# Controller_Keinz_2022.net
KiCad netlist of a schematic drawn in EAGLE
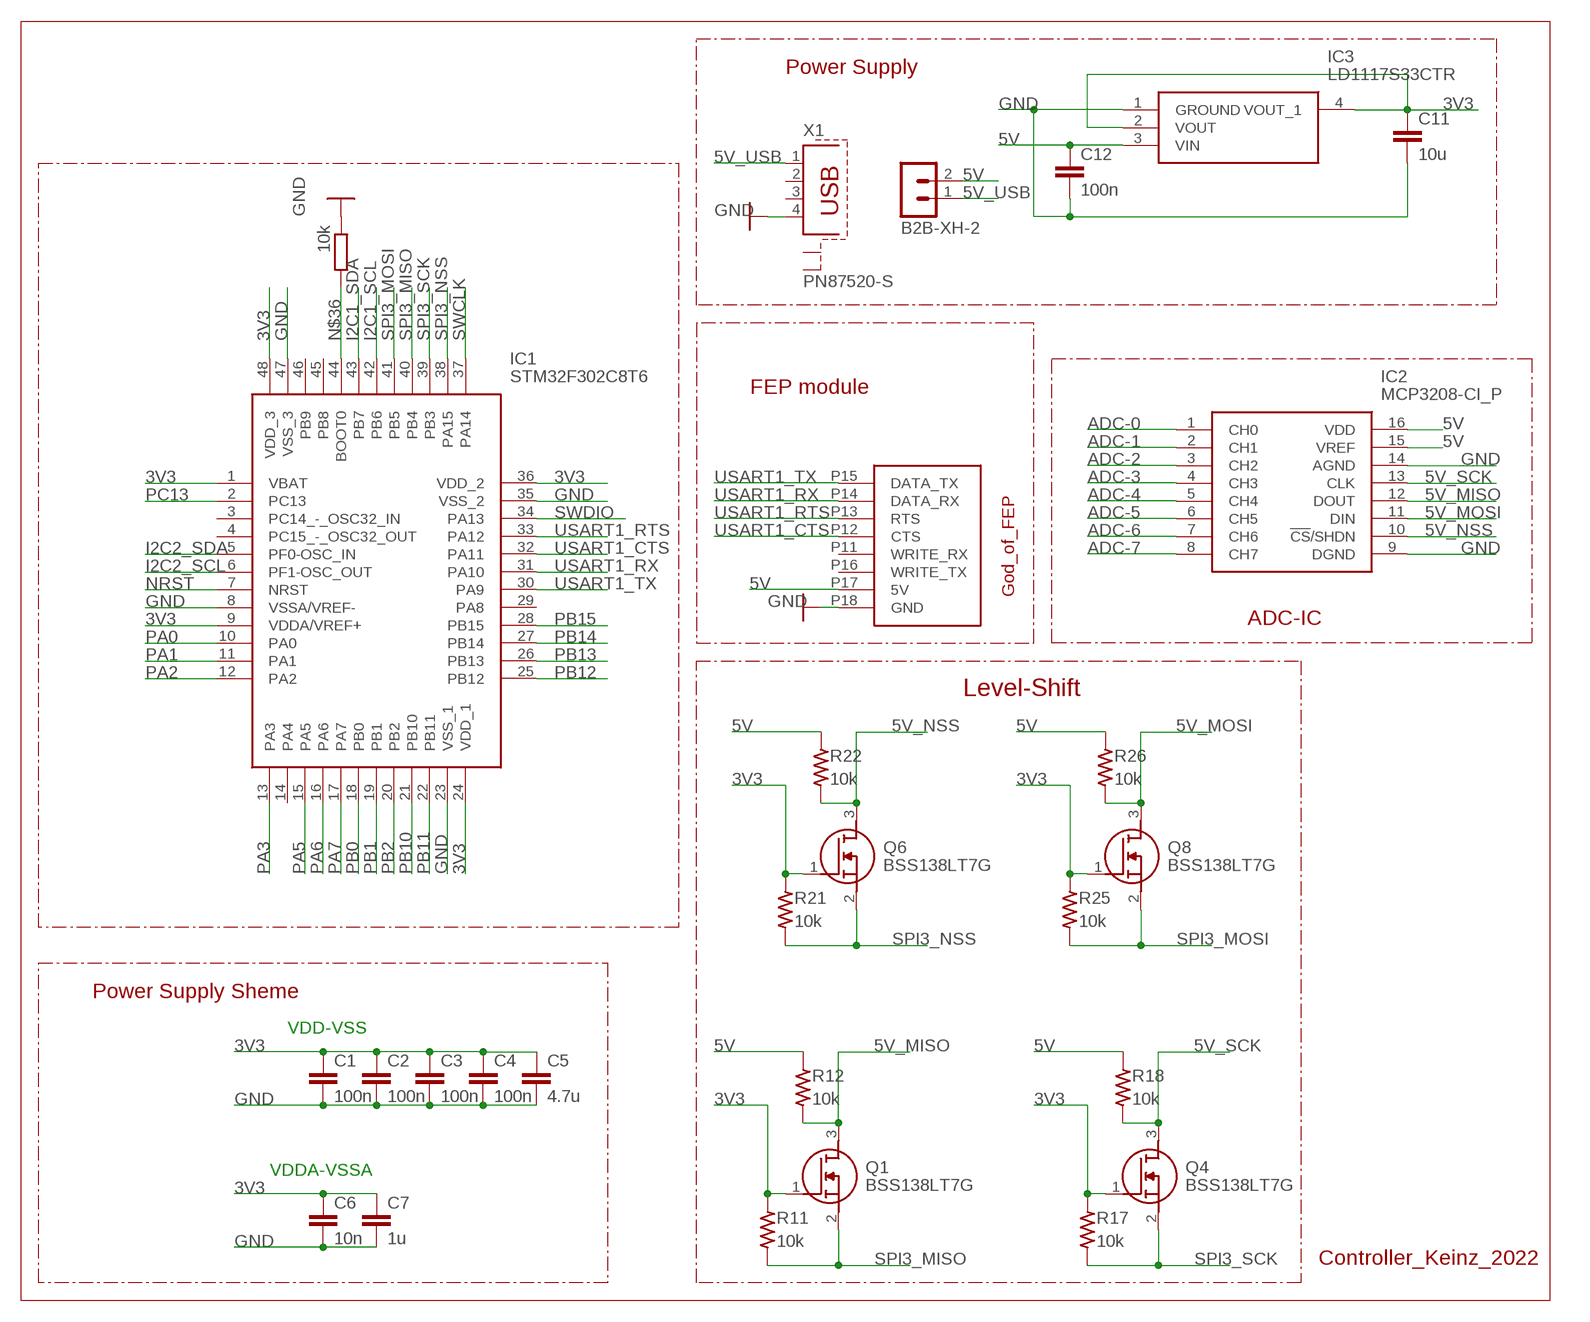
[diagram p0: schematic, sheet 1]
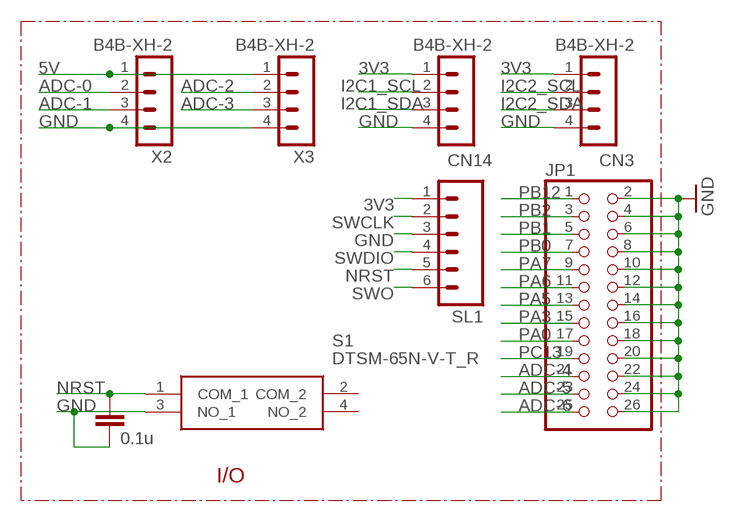
[diagram p1: schematic, sheet 2]
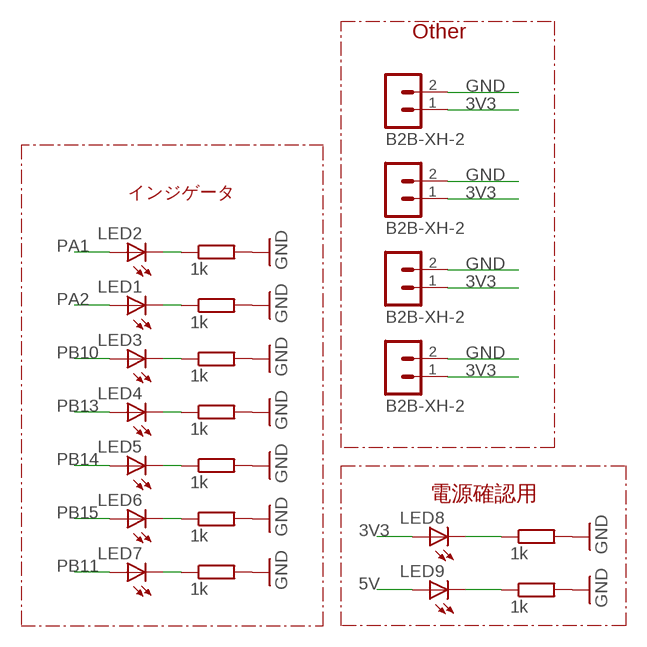
[diagram p2: schematic, sheet 3]

(export (version "E")
  (design (tool "Eeschema 10.0.6"))
  (components
    (comp (ref "C1")
      (value "100n")
      (footprint "eagle-import:C0603K")
      (libsource (lib "eagle-import") (part "C-EUC0603K"))
    )
    (comp (ref "C2")
      (value "100n")
      (footprint "eagle-import:C0603K")
      (libsource (lib "eagle-import") (part "C-EUC0603K"))
    )
    (comp (ref "C3")
      (value "100n")
      (footprint "eagle-import:C0603K")
      (libsource (lib "eagle-import") (part "C-EUC0603K"))
    )
    (comp (ref "C4")
      (value "100n")
      (footprint "eagle-import:C0603K")
      (libsource (lib "eagle-import") (part "C-EUC0603K"))
    )
    (comp (ref "C5")
      (value "4.7u")
      (footprint "eagle-import:C0603K")
      (libsource (lib "eagle-import") (part "C-EUC0603K"))
    )
    (comp (ref "C6")
      (value "10n")
      (footprint "eagle-import:C0603K")
      (libsource (lib "eagle-import") (part "C-EUC0603K"))
    )
    (comp (ref "C7")
      (value "1u")
      (footprint "eagle-import:C0603K")
      (libsource (lib "eagle-import") (part "C-EUC0603K"))
    )
    (comp (ref "C11")
      (value "10u")
      (footprint "eagle-import:C0603K")
      (libsource (lib "eagle-import") (part "C-EUC0603K"))
    )
    (comp (ref "C12")
      (value "100n")
      (footprint "eagle-import:C0603K")
      (libsource (lib "eagle-import") (part "C-EUC0603K"))
    )
    (comp (ref "FEP_1")
      (value "GOD_OF_FEP")
      (footprint "eagle-import:GOD_OF_FEP")
      (libsource (lib "eagle-import") (part "GOD_OF_FEP"))
    )
    (comp (ref "IC1")
      (value "STM32F302C8T6")
      (footprint "eagle-import:QFP50P900X900X160-48N")
      (fields (field (name "MOUSER_PART_NUMBER") "511-STM32F302C8T6"))
      (libsource (lib "eagle-import") (part "STM32F302C8T6"))
    )
    (comp (ref "IC2")
      (value "MCP3208-CI_P")
      (footprint "eagle-import:DIP781W56P254L1918H533Q16N")
      (fields
        (field (name "ARROW_PART_NUMBER") "MCP3208-CI/P")
        (field (name "MOUSER_PART_NUMBER") "579-MCP3208CIP")
      )
      (libsource (lib "eagle-import") (part "MCP3208-CI_P"))
    )
    (comp (ref "IC3")
      (value "LD1117S33CTR")
      (footprint "eagle-import:SOT230P700X190-4N")
      (fields (field (name "MOUSER_PART_NUMBER") "511-LD1117S33C") (field (name "RS_PART_NUMBER") "6869388P"))
      (libsource (lib "eagle-import") (part "LD1117S33CTR"))
    )
    (comp (ref "Q1")
      (value "BSS138LT7G")
      (footprint "eagle-import:SOT96P237X111-3N")
      (fields (field (name "MOUSER_PART_NUMBER") "863-BSS138LT7G"))
      (libsource (lib "eagle-import") (part "BSS138LT7G"))
    )
    (comp (ref "Q4")
      (value "BSS138LT7G")
      (footprint "eagle-import:SOT96P237X111-3N")
      (fields (field (name "MOUSER_PART_NUMBER") "863-BSS138LT7G"))
      (libsource (lib "eagle-import") (part "BSS138LT7G"))
    )
    (comp (ref "Q6")
      (value "BSS138LT7G")
      (footprint "eagle-import:SOT96P237X111-3N")
      (fields (field (name "MOUSER_PART_NUMBER") "863-BSS138LT7G"))
      (libsource (lib "eagle-import") (part "BSS138LT7G"))
    )
    (comp (ref "Q8")
      (value "BSS138LT7G")
      (footprint "eagle-import:SOT96P237X111-3N")
      (fields (field (name "MOUSER_PART_NUMBER") "863-BSS138LT7G"))
      (libsource (lib "eagle-import") (part "BSS138LT7G"))
    )
    (comp (ref "R8")
      (value "10k")
      (footprint "eagle-import:R0603@1")
      (libsource (lib "eagle-import") (part "R-EU_R0603"))
    )
    (comp (ref "R11")
      (value "10k")
      (footprint "eagle-import:SMD1608")
      (libsource (lib "eagle-import") (part "RESISTOR-US1608"))
    )
    (comp (ref "R12")
      (value "10k")
      (footprint "eagle-import:SMD1608")
      (libsource (lib "eagle-import") (part "RESISTOR-US1608"))
    )
    (comp (ref "R17")
      (value "10k")
      (footprint "eagle-import:SMD1608")
      (libsource (lib "eagle-import") (part "RESISTOR-US1608"))
    )
    (comp (ref "R18")
      (value "10k")
      (footprint "eagle-import:SMD1608")
      (libsource (lib "eagle-import") (part "RESISTOR-US1608"))
    )
    (comp (ref "R21")
      (value "10k")
      (footprint "eagle-import:SMD1608")
      (libsource (lib "eagle-import") (part "RESISTOR-US1608"))
    )
    (comp (ref "R22")
      (value "10k")
      (footprint "eagle-import:SMD1608")
      (libsource (lib "eagle-import") (part "RESISTOR-US1608"))
    )
    (comp (ref "R25")
      (value "10k")
      (footprint "eagle-import:SMD1608")
      (libsource (lib "eagle-import") (part "RESISTOR-US1608"))
    )
    (comp (ref "R26")
      (value "10k")
      (footprint "eagle-import:SMD1608")
      (libsource (lib "eagle-import") (part "RESISTOR-US1608"))
    )
    (comp (ref "X1")
      (value "PN87520-S")
      (footprint "eagle-import:PN87520-S")
      (libsource (lib "eagle-import") (part "PN87520-S"))
    )
    (comp (ref "X22")
      (value "B2B-XH-2")
      (footprint "eagle-import:B2B-XH-A")
      (libsource (lib "eagle-import") (part "B2B-XH-2"))
    )
    (comp (ref "LED1")
      (value "LEDCHIP-LED0805")
      (footprint "eagle-import:CHIP-LED0805")
      (libsource (lib "eagle-import") (part "LEDCHIP-LED0805"))
    )
    (comp (ref "LED2")
      (value "LEDCHIP-LED0805")
      (footprint "eagle-import:CHIP-LED0805")
      (libsource (lib "eagle-import") (part "LEDCHIP-LED0805"))
    )
    (comp (ref "LED3")
      (value "LEDCHIP-LED0805")
      (footprint "eagle-import:CHIP-LED0805")
      (libsource (lib "eagle-import") (part "LEDCHIP-LED0805"))
    )
    (comp (ref "LED4")
      (value "LEDCHIP-LED0805")
      (footprint "eagle-import:CHIP-LED0805")
      (libsource (lib "eagle-import") (part "LEDCHIP-LED0805"))
    )
    (comp (ref "LED5")
      (value "LEDCHIP-LED0805")
      (footprint "eagle-import:CHIP-LED0805")
      (libsource (lib "eagle-import") (part "LEDCHIP-LED0805"))
    )
    (comp (ref "LED6")
      (value "LEDCHIP-LED0805")
      (footprint "eagle-import:CHIP-LED0805")
      (libsource (lib "eagle-import") (part "LEDCHIP-LED0805"))
    )
    (comp (ref "LED7")
      (value "LEDCHIP-LED0805")
      (footprint "eagle-import:CHIP-LED0805")
      (libsource (lib "eagle-import") (part "LEDCHIP-LED0805"))
    )
    (comp (ref "LED8")
      (value "LEDCHIP-LED0805")
      (footprint "eagle-import:CHIP-LED0805")
      (libsource (lib "eagle-import") (part "LEDCHIP-LED0805"))
    )
    (comp (ref "LED9")
      (value "LEDCHIP-LED0805")
      (footprint "eagle-import:CHIP-LED0805")
      (libsource (lib "eagle-import") (part "LEDCHIP-LED0805"))
    )
    (comp (ref "R1")
      (value "1k")
      (footprint "eagle-import:R0603@1")
      (libsource (lib "eagle-import") (part "R-EU_R0603"))
    )
    (comp (ref "R2")
      (value "1k")
      (footprint "eagle-import:R0603@1")
      (libsource (lib "eagle-import") (part "R-EU_R0603"))
    )
    (comp (ref "R3")
      (value "1k")
      (footprint "eagle-import:R0603@1")
      (libsource (lib "eagle-import") (part "R-EU_R0603"))
    )
    (comp (ref "R4")
      (value "1k")
      (footprint "eagle-import:R0603@1")
      (libsource (lib "eagle-import") (part "R-EU_R0603"))
    )
    (comp (ref "R5")
      (value "1k")
      (footprint "eagle-import:R0603@1")
      (libsource (lib "eagle-import") (part "R-EU_R0603"))
    )
    (comp (ref "R6")
      (value "1k")
      (footprint "eagle-import:R0603@1")
      (libsource (lib "eagle-import") (part "R-EU_R0603"))
    )
    (comp (ref "R7")
      (value "1k")
      (footprint "eagle-import:R0603@1")
      (libsource (lib "eagle-import") (part "R-EU_R0603"))
    )
    (comp (ref "R9")
      (value "1k")
      (footprint "eagle-import:R0603@1")
      (libsource (lib "eagle-import") (part "R-EU_R0603"))
    )
    (comp (ref "R10")
      (value "1k")
      (footprint "eagle-import:R0603@1")
      (libsource (lib "eagle-import") (part "R-EU_R0603"))
    )
    (comp (ref "X4")
      (value "B2B-XH-2")
      (footprint "eagle-import:B2B-XH-A")
      (libsource (lib "eagle-import") (part "B2B-XH-2"))
    )
    (comp (ref "X5")
      (value "B2B-XH-2")
      (footprint "eagle-import:B2B-XH-A")
      (libsource (lib "eagle-import") (part "B2B-XH-2"))
    )
    (comp (ref "X6")
      (value "B2B-XH-2")
      (footprint "eagle-import:B2B-XH-A")
      (libsource (lib "eagle-import") (part "B2B-XH-2"))
    )
    (comp (ref "X7")
      (value "B2B-XH-2")
      (footprint "eagle-import:B2B-XH-A")
      (libsource (lib "eagle-import") (part "B2B-XH-2"))
    )
    (comp (ref "C13")
      (value "0.1u")
      (footprint "eagle-import:C0603K")
      (libsource (lib "eagle-import") (part "C-EUC0603K"))
    )
    (comp (ref "CN3")
      (value "B4B-XH-2")
      (footprint "eagle-import:B4B-XH-A")
      (libsource (lib "eagle-import") (part "B4B-XH-2"))
    )
    (comp (ref "CN14")
      (value "B4B-XH-2")
      (footprint "eagle-import:B4B-XH-A")
      (libsource (lib "eagle-import") (part "B4B-XH-2"))
    )
    (comp (ref "JP1")
      (value "PINHD-2X13")
      (footprint "eagle-import:2X13")
      (libsource (lib "eagle-import") (part "PINHD-2X13"))
    )
    (comp (ref "S1")
      (value "DTSM-65N-V-T_R")
      (footprint "eagle-import:DTSM65NVTR")
      (fields
        (field (name "MANUFACTURER_PART_NUMBER") "DTSM-65N-V-T/R")
        (field (name "MOUSER_PART_NUMBER") "113-DTSM-65N-V-T/R")
      )
      (libsource (lib "eagle-import") (part "DTSM-65N-V-T_R"))
    )
    (comp (ref "SL1")
      (value "MA06")
      (footprint "eagle-import:06PA")
      (libsource (lib "eagle-import") (part "MA06"))
    )
    (comp (ref "X2")
      (value "B4B-XH-2")
      (footprint "eagle-import:B4B-XH-A")
      (libsource (lib "eagle-import") (part "B4B-XH-2"))
    )
    (comp (ref "X3")
      (value "B4B-XH-2")
      (footprint "eagle-import:B4B-XH-A")
      (libsource (lib "eagle-import") (part "B4B-XH-2"))
    )
  )
  (nets
    (net (code "1") (name "3V3") (class "Default")
      (node (ref "C1") (pin "1") (pinfunction "1_1") (pintype "passive"))
      (node (ref "C11") (pin "1") (pinfunction "1_1") (pintype "passive"))
      (node (ref "C2") (pin "1") (pinfunction "1_1") (pintype "passive"))
      (node (ref "C3") (pin "1") (pinfunction "1_1") (pintype "passive"))
      (node (ref "C4") (pin "1") (pinfunction "1_1") (pintype "passive"))
      (node (ref "C5") (pin "1") (pinfunction "1_1") (pintype "passive"))
      (node (ref "C6") (pin "1") (pinfunction "1_1") (pintype "passive"))
      (node (ref "C7") (pin "1") (pinfunction "1_1") (pintype "passive"))
      (node (ref "CN14") (pin "1") (pinfunction "1_1") (pintype "passive"))
      (node (ref "CN3") (pin "1") (pinfunction "1_1") (pintype "passive"))
      (node (ref "IC1") (pin "1") (pinfunction "VBAT_1") (pintype "power_in"))
      (node (ref "IC1") (pin "24") (pinfunction "VDD_1_24") (pintype "power_in"))
      (node (ref "IC1") (pin "36") (pinfunction "VDD_2_36") (pintype "power_in"))
      (node (ref "IC1") (pin "48") (pinfunction "VDD_3_48") (pintype "power_in"))
      (node (ref "IC1") (pin "9") (pinfunction "VDDA/VREF+_9") (pintype "power_in"))
      (node (ref "IC3") (pin "2") (pinfunction "VOUT_2") (pintype "output"))
      (node (ref "IC3") (pin "4") (pinfunction "VOUT_1_4") (pintype "output"))
      (node (ref "LED8") (pin "A") (pinfunction "A_A") (pintype "passive"))
      (node (ref "Q1") (pin "1") (pinfunction "G_1") (pintype "bidirectional"))
      (node (ref "Q4") (pin "1") (pinfunction "G_1") (pintype "bidirectional"))
      (node (ref "Q6") (pin "1") (pinfunction "G_1") (pintype "bidirectional"))
      (node (ref "Q8") (pin "1") (pinfunction "G_1") (pintype "bidirectional"))
      (node (ref "R11") (pin "1") (pinfunction "1_1") (pintype "passive"))
      (node (ref "R17") (pin "1") (pinfunction "1_1") (pintype "passive"))
      (node (ref "R21") (pin "1") (pinfunction "1_1") (pintype "passive"))
      (node (ref "R25") (pin "1") (pinfunction "1_1") (pintype "passive"))
      (node (ref "SL1") (pin "1") (pinfunction "1_1") (pintype "passive"))
      (node (ref "X4") (pin "1") (pinfunction "1_1") (pintype "passive"))
      (node (ref "X5") (pin "1") (pinfunction "1_1") (pintype "passive"))
      (node (ref "X6") (pin "1") (pinfunction "1_1") (pintype "passive"))
      (node (ref "X7") (pin "1") (pinfunction "1_1") (pintype "passive"))
    )
    (net (code "2") (name "5V") (class "Default")
      (node (ref "C12") (pin "1") (pinfunction "1_1") (pintype "passive"))
      (node (ref "FEP_1") (pin "P17") (pinfunction "5V_P17") (pintype "bidirectional"))
      (node (ref "IC2") (pin "15") (pinfunction "VREF_15") (pintype "bidirectional"))
      (node (ref "IC2") (pin "16") (pinfunction "VDD_16") (pintype "bidirectional"))
      (node (ref "IC3") (pin "3") (pinfunction "VIN_3") (pintype "input"))
      (node (ref "LED9") (pin "A") (pinfunction "A_A") (pintype "passive"))
      (node (ref "R12") (pin "1") (pinfunction "1_1") (pintype "passive"))
      (node (ref "R18") (pin "1") (pinfunction "1_1") (pintype "passive"))
      (node (ref "R22") (pin "1") (pinfunction "1_1") (pintype "passive"))
      (node (ref "R26") (pin "1") (pinfunction "1_1") (pintype "passive"))
      (node (ref "X2") (pin "1") (pinfunction "1_1") (pintype "passive"))
      (node (ref "X22") (pin "2") (pinfunction "2_2") (pintype "passive"))
      (node (ref "X3") (pin "1") (pinfunction "1_1") (pintype "passive"))
    )
    (net (code "3") (name "5V_MISO") (class "Default")
      (node (ref "IC2") (pin "12") (pinfunction "DOUT_12") (pintype "bidirectional"))
      (node (ref "Q1") (pin "3") (pinfunction "D_3") (pintype "bidirectional"))
      (node (ref "R12") (pin "2") (pinfunction "2_2") (pintype "passive"))
    )
    (net (code "4") (name "5V_MOSI") (class "Default")
      (node (ref "IC2") (pin "11") (pinfunction "DIN_11") (pintype "bidirectional"))
      (node (ref "Q8") (pin "3") (pinfunction "D_3") (pintype "bidirectional"))
      (node (ref "R26") (pin "2") (pinfunction "2_2") (pintype "passive"))
    )
    (net (code "5") (name "5V_NSS") (class "Default")
      (node (ref "IC2") (pin "10") (pinfunction "~{CS}/SHDN_10") (pintype "bidirectional"))
      (node (ref "Q6") (pin "3") (pinfunction "D_3") (pintype "bidirectional"))
      (node (ref "R22") (pin "2") (pinfunction "2_2") (pintype "passive"))
    )
    (net (code "6") (name "5V_SCK") (class "Default")
      (node (ref "IC2") (pin "13") (pinfunction "CLK_13") (pintype "bidirectional"))
      (node (ref "Q4") (pin "3") (pinfunction "D_3") (pintype "bidirectional"))
      (node (ref "R18") (pin "2") (pinfunction "2_2") (pintype "passive"))
    )
    (net (code "7") (name "5V_USB") (class "Default")
      (node (ref "X1") (pin "1") (pinfunction "1_1") (pintype "passive"))
      (node (ref "X22") (pin "1") (pinfunction "1_1") (pintype "passive"))
    )
    (net (code "8") (name "ADC-0") (class "Default")
      (node (ref "IC2") (pin "1") (pinfunction "CH0_1") (pintype "bidirectional"))
      (node (ref "X2") (pin "2") (pinfunction "2_2") (pintype "passive"))
    )
    (net (code "9") (name "ADC-1") (class "Default")
      (node (ref "IC2") (pin "2") (pinfunction "CH1_2") (pintype "bidirectional"))
      (node (ref "X2") (pin "3") (pinfunction "3_3") (pintype "passive"))
    )
    (net (code "10") (name "ADC-2") (class "Default")
      (node (ref "IC2") (pin "3") (pinfunction "CH2_3") (pintype "bidirectional"))
      (node (ref "X3") (pin "2") (pinfunction "2_2") (pintype "passive"))
    )
    (net (code "11") (name "ADC-3") (class "Default")
      (node (ref "IC2") (pin "4") (pinfunction "CH3_4") (pintype "bidirectional"))
      (node (ref "X3") (pin "3") (pinfunction "3_3") (pintype "passive"))
    )
    (net (code "12") (name "ADC-4") (class "Default")
      (node (ref "IC2") (pin "5") (pinfunction "CH4_5") (pintype "bidirectional"))
      (node (ref "JP1") (pin "21") (pinfunction "21_21") (pintype "passive"))
    )
    (net (code "13") (name "ADC-5") (class "Default")
      (node (ref "IC2") (pin "6") (pinfunction "CH5_6") (pintype "bidirectional"))
      (node (ref "JP1") (pin "23") (pinfunction "23_23") (pintype "passive"))
    )
    (net (code "14") (name "ADC-6") (class "Default")
      (node (ref "IC2") (pin "7") (pinfunction "CH6_7") (pintype "bidirectional"))
      (node (ref "JP1") (pin "25") (pinfunction "25_25") (pintype "passive"))
    )
    (net (code "15") (name "ADC-7") (class "Default")
      (node (ref "IC2") (pin "8") (pinfunction "CH7_8") (pintype "bidirectional"))
    )
    (net (code "16") (name "GND") (class "Default")
      (node (ref "C1") (pin "2") (pinfunction "2_2") (pintype "passive"))
      (node (ref "C11") (pin "2") (pinfunction "2_2") (pintype "passive"))
      (node (ref "C12") (pin "2") (pinfunction "2_2") (pintype "passive"))
      (node (ref "C13") (pin "2") (pinfunction "2_2") (pintype "passive"))
      (node (ref "C2") (pin "2") (pinfunction "2_2") (pintype "passive"))
      (node (ref "C3") (pin "2") (pinfunction "2_2") (pintype "passive"))
      (node (ref "C4") (pin "2") (pinfunction "2_2") (pintype "passive"))
      (node (ref "C5") (pin "2") (pinfunction "2_2") (pintype "passive"))
      (node (ref "C6") (pin "2") (pinfunction "2_2") (pintype "passive"))
      (node (ref "C7") (pin "2") (pinfunction "2_2") (pintype "passive"))
      (node (ref "CN14") (pin "4") (pinfunction "4_4") (pintype "passive"))
      (node (ref "CN3") (pin "4") (pinfunction "4_4") (pintype "passive"))
      (node (ref "FEP_1") (pin "P18") (pinfunction "GND_P18") (pintype "bidirectional"))
      (node (ref "IC1") (pin "23") (pinfunction "VSS_1_23") (pintype "power_in"))
      (node (ref "IC1") (pin "35") (pinfunction "VSS_2_35") (pintype "power_in"))
      (node (ref "IC1") (pin "47") (pinfunction "VSS_3_47") (pintype "power_in"))
      (node (ref "IC1") (pin "8") (pinfunction "VSSA/VREF-_8") (pintype "power_in"))
      (node (ref "IC2") (pin "14") (pinfunction "AGND_14") (pintype "bidirectional"))
      (node (ref "IC2") (pin "9") (pinfunction "DGND_9") (pintype "bidirectional"))
      (node (ref "IC3") (pin "1") (pinfunction "GROUND_1") (pintype "bidirectional"))
      (node (ref "JP1") (pin "10") (pinfunction "10_10") (pintype "passive"))
      (node (ref "JP1") (pin "12") (pinfunction "12_12") (pintype "passive"))
      (node (ref "JP1") (pin "14") (pinfunction "14_14") (pintype "passive"))
      (node (ref "JP1") (pin "16") (pinfunction "16_16") (pintype "passive"))
      (node (ref "JP1") (pin "18") (pinfunction "18_18") (pintype "passive"))
      (node (ref "JP1") (pin "2") (pinfunction "2_2") (pintype "passive"))
      (node (ref "JP1") (pin "20") (pinfunction "20_20") (pintype "passive"))
      (node (ref "JP1") (pin "22") (pinfunction "22_22") (pintype "passive"))
      (node (ref "JP1") (pin "24") (pinfunction "24_24") (pintype "passive"))
      (node (ref "JP1") (pin "26") (pinfunction "26_26") (pintype "passive"))
      (node (ref "JP1") (pin "4") (pinfunction "4_4") (pintype "passive"))
      (node (ref "JP1") (pin "6") (pinfunction "6_6") (pintype "passive"))
      (node (ref "JP1") (pin "8") (pinfunction "8_8") (pintype "passive"))
      (node (ref "R1") (pin "2") (pinfunction "2_2") (pintype "passive"))
      (node (ref "R10") (pin "2") (pinfunction "2_2") (pintype "passive"))
      (node (ref "R2") (pin "2") (pinfunction "2_2") (pintype "passive"))
      (node (ref "R3") (pin "2") (pinfunction "2_2") (pintype "passive"))
      (node (ref "R4") (pin "2") (pinfunction "2_2") (pintype "passive"))
      (node (ref "R5") (pin "2") (pinfunction "2_2") (pintype "passive"))
      (node (ref "R6") (pin "2") (pinfunction "2_2") (pintype "passive"))
      (node (ref "R7") (pin "2") (pinfunction "2_2") (pintype "passive"))
      (node (ref "R8") (pin "1") (pinfunction "1_1") (pintype "passive"))
      (node (ref "R9") (pin "2") (pinfunction "2_2") (pintype "passive"))
      (node (ref "S1") (pin "3") (pinfunction "NO_1_3") (pintype "bidirectional"))
      (node (ref "SL1") (pin "3") (pinfunction "3_3") (pintype "passive"))
      (node (ref "X1") (pin "4") (pinfunction "4_4") (pintype "passive"))
      (node (ref "X2") (pin "4") (pinfunction "4_4") (pintype "passive"))
      (node (ref "X3") (pin "4") (pinfunction "4_4") (pintype "passive"))
      (node (ref "X4") (pin "2") (pinfunction "2_2") (pintype "passive"))
      (node (ref "X5") (pin "2") (pinfunction "2_2") (pintype "passive"))
      (node (ref "X6") (pin "2") (pinfunction "2_2") (pintype "passive"))
      (node (ref "X7") (pin "2") (pinfunction "2_2") (pintype "passive"))
    )
    (net (code "17") (name "I2C1_SCL") (class "Default")
      (node (ref "CN14") (pin "2") (pinfunction "2_2") (pintype "passive"))
      (node (ref "IC1") (pin "42") (pinfunction "PB6_42") (pintype "bidirectional"))
    )
    (net (code "18") (name "I2C1_SDA") (class "Default")
      (node (ref "CN14") (pin "3") (pinfunction "3_3") (pintype "passive"))
      (node (ref "IC1") (pin "43") (pinfunction "PB7_43") (pintype "bidirectional"))
    )
    (net (code "19") (name "I2C2_SCL") (class "Default")
      (node (ref "CN3") (pin "2") (pinfunction "2_2") (pintype "passive"))
      (node (ref "IC1") (pin "6") (pinfunction "PF1-OSC_OUT_6") (pintype "bidirectional"))
    )
    (net (code "20") (name "I2C2_SDA") (class "Default")
      (node (ref "CN3") (pin "3") (pinfunction "3_3") (pintype "passive"))
      (node (ref "IC1") (pin "5") (pinfunction "PF0-OSC_IN_5") (pintype "bidirectional"))
    )
    (net (code "21") (name "N$36") (class "Default")
      (node (ref "IC1") (pin "44") (pinfunction "BOOT0_44") (pintype "bidirectional"))
      (node (ref "R8") (pin "2") (pinfunction "2_2") (pintype "passive"))
    )
    (net (code "22") (name "NRST") (class "Default")
      (node (ref "C13") (pin "1") (pinfunction "1_1") (pintype "passive"))
      (node (ref "IC1") (pin "7") (pinfunction "NRST_7") (pintype "bidirectional"))
      (node (ref "S1") (pin "1") (pinfunction "COM_1_1") (pintype "bidirectional"))
      (node (ref "SL1") (pin "5") (pinfunction "5_5") (pintype "passive"))
    )
    (net (code "23") (name "Net-(LED1-PadC)") (class "Default")
      (node (ref "LED1") (pin "C") (pinfunction "C_C") (pintype "passive"))
      (node (ref "R2") (pin "1") (pinfunction "1_1") (pintype "passive"))
    )
    (net (code "24") (name "Net-(LED2-PadC)") (class "Default")
      (node (ref "LED2") (pin "C") (pinfunction "C_C") (pintype "passive"))
      (node (ref "R1") (pin "1") (pinfunction "1_1") (pintype "passive"))
    )
    (net (code "25") (name "Net-(LED3-PadC)") (class "Default")
      (node (ref "LED3") (pin "C") (pinfunction "C_C") (pintype "passive"))
      (node (ref "R3") (pin "1") (pinfunction "1_1") (pintype "passive"))
    )
    (net (code "26") (name "Net-(LED4-PadC)") (class "Default")
      (node (ref "LED4") (pin "C") (pinfunction "C_C") (pintype "passive"))
      (node (ref "R4") (pin "1") (pinfunction "1_1") (pintype "passive"))
    )
    (net (code "27") (name "Net-(LED5-PadC)") (class "Default")
      (node (ref "LED5") (pin "C") (pinfunction "C_C") (pintype "passive"))
      (node (ref "R5") (pin "1") (pinfunction "1_1") (pintype "passive"))
    )
    (net (code "28") (name "Net-(LED6-PadC)") (class "Default")
      (node (ref "LED6") (pin "C") (pinfunction "C_C") (pintype "passive"))
      (node (ref "R6") (pin "1") (pinfunction "1_1") (pintype "passive"))
    )
    (net (code "29") (name "Net-(LED7-PadC)") (class "Default")
      (node (ref "LED7") (pin "C") (pinfunction "C_C") (pintype "passive"))
      (node (ref "R7") (pin "1") (pinfunction "1_1") (pintype "passive"))
    )
    (net (code "30") (name "Net-(LED8-PadC)") (class "Default")
      (node (ref "LED8") (pin "C") (pinfunction "C_C") (pintype "passive"))
      (node (ref "R9") (pin "1") (pinfunction "1_1") (pintype "passive"))
    )
    (net (code "31") (name "Net-(LED9-PadC)") (class "Default")
      (node (ref "LED9") (pin "C") (pinfunction "C_C") (pintype "passive"))
      (node (ref "R10") (pin "1") (pinfunction "1_1") (pintype "passive"))
    )
    (net (code "32") (name "PA0") (class "Default")
      (node (ref "IC1") (pin "10") (pinfunction "PA0_10") (pintype "bidirectional"))
      (node (ref "JP1") (pin "17") (pinfunction "17_17") (pintype "passive"))
    )
    (net (code "33") (name "PA1") (class "Default")
      (node (ref "IC1") (pin "11") (pinfunction "PA1_11") (pintype "bidirectional"))
      (node (ref "LED2") (pin "A") (pinfunction "A_A") (pintype "passive"))
    )
    (net (code "34") (name "PA2") (class "Default")
      (node (ref "IC1") (pin "12") (pinfunction "PA2_12") (pintype "bidirectional"))
      (node (ref "LED1") (pin "A") (pinfunction "A_A") (pintype "passive"))
    )
    (net (code "35") (name "PA3") (class "Default")
      (node (ref "IC1") (pin "13") (pinfunction "PA3_13") (pintype "bidirectional"))
      (node (ref "JP1") (pin "15") (pinfunction "15_15") (pintype "passive"))
    )
    (net (code "36") (name "PA5") (class "Default")
      (node (ref "IC1") (pin "15") (pinfunction "PA5_15") (pintype "bidirectional"))
      (node (ref "JP1") (pin "13") (pinfunction "13_13") (pintype "passive"))
    )
    (net (code "37") (name "PA6") (class "Default")
      (node (ref "IC1") (pin "16") (pinfunction "PA6_16") (pintype "bidirectional"))
      (node (ref "JP1") (pin "11") (pinfunction "11_11") (pintype "passive"))
    )
    (net (code "38") (name "PA7") (class "Default")
      (node (ref "IC1") (pin "17") (pinfunction "PA7_17") (pintype "bidirectional"))
      (node (ref "JP1") (pin "9") (pinfunction "9_9") (pintype "passive"))
    )
    (net (code "39") (name "PB0") (class "Default")
      (node (ref "IC1") (pin "18") (pinfunction "PB0_18") (pintype "bidirectional"))
      (node (ref "JP1") (pin "7") (pinfunction "7_7") (pintype "passive"))
    )
    (net (code "40") (name "PB1") (class "Default")
      (node (ref "IC1") (pin "19") (pinfunction "PB1_19") (pintype "bidirectional"))
      (node (ref "JP1") (pin "5") (pinfunction "5_5") (pintype "passive"))
    )
    (net (code "41") (name "PB2") (class "Default")
      (node (ref "IC1") (pin "20") (pinfunction "PB2_20") (pintype "bidirectional"))
      (node (ref "JP1") (pin "3") (pinfunction "3_3") (pintype "passive"))
    )
    (net (code "42") (name "PB10") (class "Default")
      (node (ref "IC1") (pin "21") (pinfunction "PB10_21") (pintype "bidirectional"))
      (node (ref "LED3") (pin "A") (pinfunction "A_A") (pintype "passive"))
    )
    (net (code "43") (name "PB11") (class "Default")
      (node (ref "IC1") (pin "22") (pinfunction "PB11_22") (pintype "bidirectional"))
      (node (ref "LED7") (pin "A") (pinfunction "A_A") (pintype "passive"))
    )
    (net (code "44") (name "PB12") (class "Default")
      (node (ref "IC1") (pin "25") (pinfunction "PB12_25") (pintype "bidirectional"))
      (node (ref "JP1") (pin "1") (pinfunction "1_1") (pintype "passive"))
    )
    (net (code "45") (name "PB13") (class "Default")
      (node (ref "IC1") (pin "26") (pinfunction "PB13_26") (pintype "bidirectional"))
      (node (ref "LED4") (pin "A") (pinfunction "A_A") (pintype "passive"))
    )
    (net (code "46") (name "PB14") (class "Default")
      (node (ref "IC1") (pin "27") (pinfunction "PB14_27") (pintype "bidirectional"))
      (node (ref "LED5") (pin "A") (pinfunction "A_A") (pintype "passive"))
    )
    (net (code "47") (name "PB15") (class "Default")
      (node (ref "IC1") (pin "28") (pinfunction "PB15_28") (pintype "bidirectional"))
      (node (ref "LED6") (pin "A") (pinfunction "A_A") (pintype "passive"))
    )
    (net (code "48") (name "PC13") (class "Default")
      (node (ref "IC1") (pin "2") (pinfunction "PC13_2") (pintype "bidirectional"))
      (node (ref "JP1") (pin "19") (pinfunction "19_19") (pintype "passive"))
    )
    (net (code "49") (name "SPI3_MISO") (class "Default")
      (node (ref "IC1") (pin "40") (pinfunction "PB4_40") (pintype "bidirectional"))
      (node (ref "Q1") (pin "2") (pinfunction "S_2") (pintype "bidirectional"))
      (node (ref "R11") (pin "2") (pinfunction "2_2") (pintype "passive"))
    )
    (net (code "50") (name "SPI3_MOSI") (class "Default")
      (node (ref "IC1") (pin "41") (pinfunction "PB5_41") (pintype "bidirectional"))
      (node (ref "Q8") (pin "2") (pinfunction "S_2") (pintype "bidirectional"))
      (node (ref "R25") (pin "2") (pinfunction "2_2") (pintype "passive"))
    )
    (net (code "51") (name "SPI3_NSS") (class "Default")
      (node (ref "IC1") (pin "38") (pinfunction "PA15_38") (pintype "bidirectional"))
      (node (ref "Q6") (pin "2") (pinfunction "S_2") (pintype "bidirectional"))
      (node (ref "R21") (pin "2") (pinfunction "2_2") (pintype "passive"))
    )
    (net (code "52") (name "SPI3_SCK") (class "Default")
      (node (ref "IC1") (pin "39") (pinfunction "PB3_39") (pintype "bidirectional"))
      (node (ref "Q4") (pin "2") (pinfunction "S_2") (pintype "bidirectional"))
      (node (ref "R17") (pin "2") (pinfunction "2_2") (pintype "passive"))
    )
    (net (code "53") (name "SWCLK") (class "Default")
      (node (ref "IC1") (pin "37") (pinfunction "PA14_37") (pintype "bidirectional"))
      (node (ref "SL1") (pin "2") (pinfunction "2_2") (pintype "passive"))
    )
    (net (code "54") (name "SWDIO") (class "Default")
      (node (ref "IC1") (pin "34") (pinfunction "PA13_34") (pintype "bidirectional"))
      (node (ref "SL1") (pin "4") (pinfunction "4_4") (pintype "passive"))
    )
    (net (code "55") (name "SWO") (class "Default")
      (node (ref "SL1") (pin "6") (pinfunction "6_6") (pintype "passive"))
    )
    (net (code "56") (name "USART1_CTS") (class "Default")
      (node (ref "FEP_1") (pin "P12") (pinfunction "CTS_P12") (pintype "bidirectional"))
      (node (ref "IC1") (pin "32") (pinfunction "PA11_32") (pintype "bidirectional"))
    )
    (net (code "57") (name "USART1_RTS") (class "Default")
      (node (ref "FEP_1") (pin "P13") (pinfunction "RTS_P13") (pintype "bidirectional"))
      (node (ref "IC1") (pin "33") (pinfunction "PA12_33") (pintype "bidirectional"))
    )
    (net (code "58") (name "USART1_RX") (class "Default")
      (node (ref "FEP_1") (pin "P14") (pinfunction "DATA_RX_P14") (pintype "bidirectional"))
      (node (ref "IC1") (pin "31") (pinfunction "PA10_31") (pintype "bidirectional"))
    )
    (net (code "59") (name "USART1_TX") (class "Default")
      (node (ref "FEP_1") (pin "P15") (pinfunction "DATA_TX_P15") (pintype "bidirectional"))
      (node (ref "IC1") (pin "30") (pinfunction "PA9_30") (pintype "bidirectional"))
    )
    (net (code "60") (name "unconnected-(FEP_1-WRITE_RX-PadP11)") (class "Default")
      (node (ref "FEP_1") (pin "P11") (pinfunction "WRITE_RX_P11") (pintype "bidirectional"))
    )
    (net (code "61") (name "unconnected-(FEP_1-WRITE_TX-PadP16)") (class "Default")
      (node (ref "FEP_1") (pin "P16") (pinfunction "WRITE_TX_P16") (pintype "bidirectional"))
    )
    (net (code "62") (name "unconnected-(IC1-PA4-Pad14)") (class "Default")
      (node (ref "IC1") (pin "14") (pinfunction "PA4_14") (pintype "bidirectional"))
    )
    (net (code "63") (name "unconnected-(IC1-PA8-Pad29)") (class "Default")
      (node (ref "IC1") (pin "29") (pinfunction "PA8_29") (pintype "bidirectional"))
    )
    (net (code "64") (name "unconnected-(IC1-PB8-Pad45)") (class "Default")
      (node (ref "IC1") (pin "45") (pinfunction "PB8_45") (pintype "bidirectional"))
    )
    (net (code "65") (name "unconnected-(IC1-PB9-Pad46)") (class "Default")
      (node (ref "IC1") (pin "46") (pinfunction "PB9_46") (pintype "bidirectional"))
    )
    (net (code "66") (name "unconnected-(IC1-PC14_-_OSC32_IN-Pad3)") (class "Default")
      (node (ref "IC1") (pin "3") (pinfunction "PC14_-_OSC32_IN_3") (pintype "bidirectional"))
    )
    (net (code "67") (name "unconnected-(IC1-PC15_-_OSC32_OUT-Pad4)") (class "Default")
      (node (ref "IC1") (pin "4") (pinfunction "PC15_-_OSC32_OUT_4") (pintype "bidirectional"))
    )
    (net (code "68") (name "unconnected-(S1-COM_2-Pad2)") (class "Default")
      (node (ref "S1") (pin "2") (pinfunction "COM_2_2") (pintype "bidirectional"))
    )
    (net (code "69") (name "unconnected-(S1-NO_2-Pad4)") (class "Default")
      (node (ref "S1") (pin "4") (pinfunction "NO_2_4") (pintype "bidirectional"))
    )
    (net (code "70") (name "unconnected-(X1-Pad2)") (class "Default")
      (node (ref "X1") (pin "2") (pinfunction "2_2") (pintype "passive"))
    )
    (net (code "71") (name "unconnected-(X1-Pad3)") (class "Default")
      (node (ref "X1") (pin "3") (pinfunction "3_3") (pintype "passive"))
    )
    (net (code "72") (name "unconnected-(X1-PadS1)") (class "Default")
      (node (ref "X1") (pin "S1") (pinfunction "S1_S1") (pintype "passive"))
    )
    (net (code "73") (name "unconnected-(X1-PadS2)") (class "Default")
      (node (ref "X1") (pin "S2") (pinfunction "S2_S2") (pintype "passive"))
    )
  )
)
